# MEMORY.net
KiCad netlist of a schematic drawn in Altium Designer
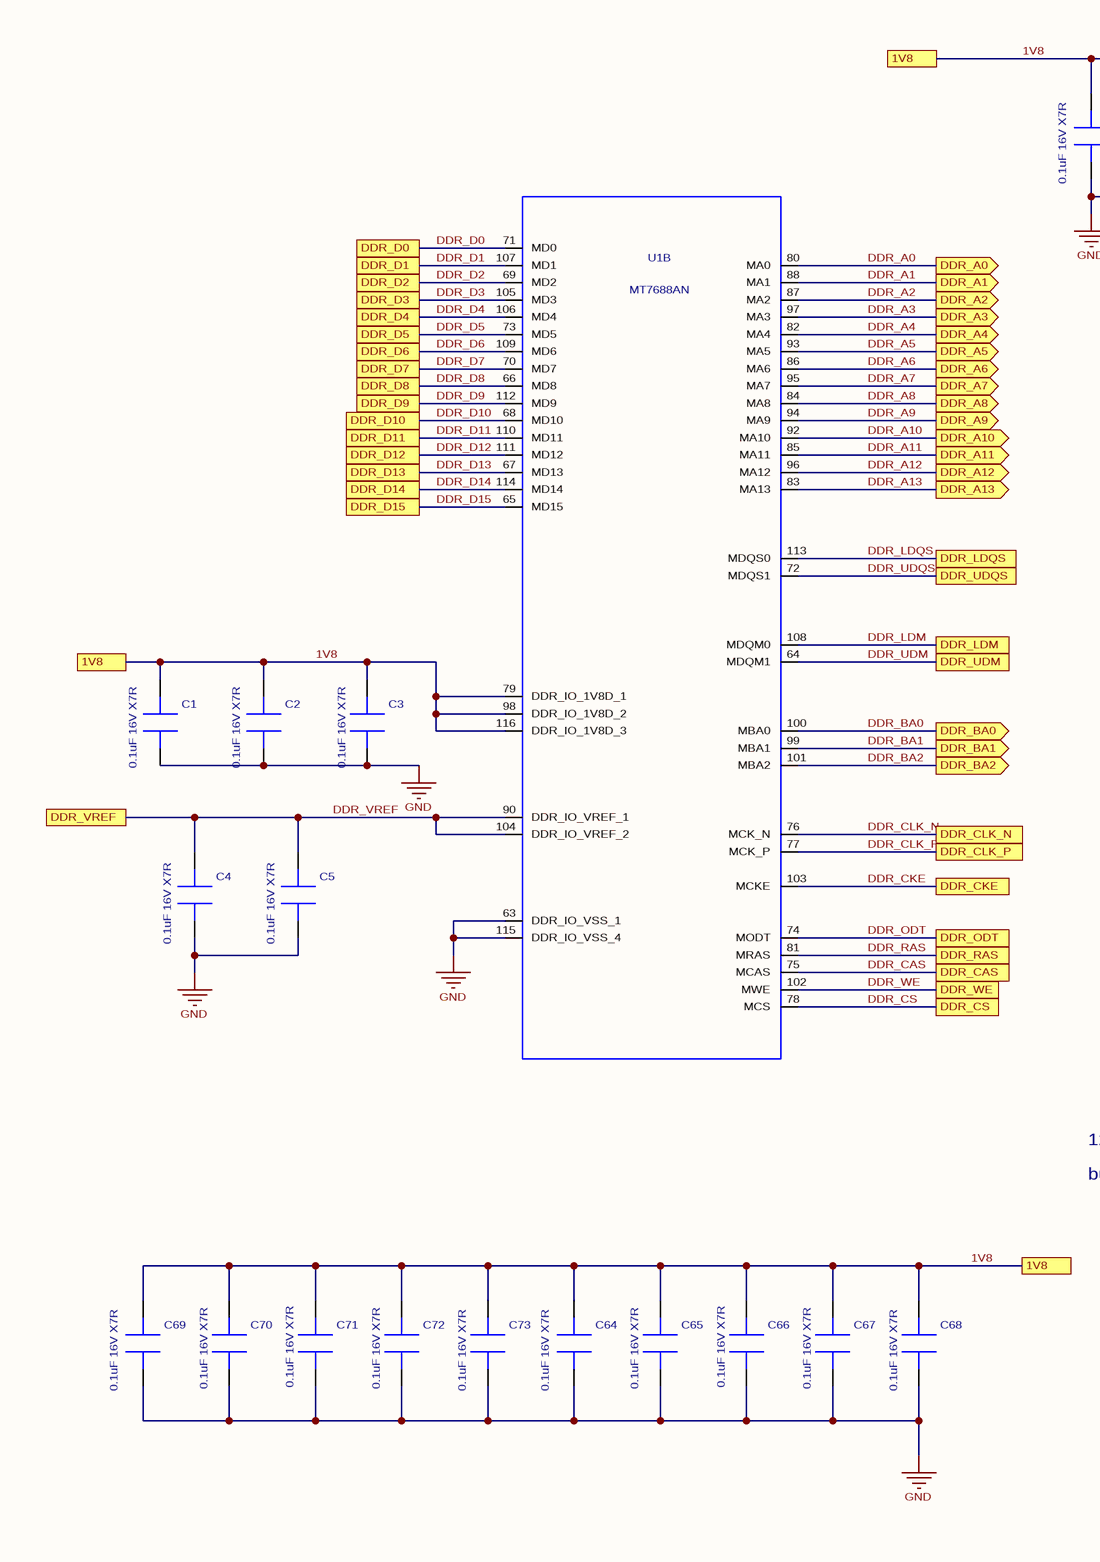
[diagram p0: MEMORY.SchDoc, left]
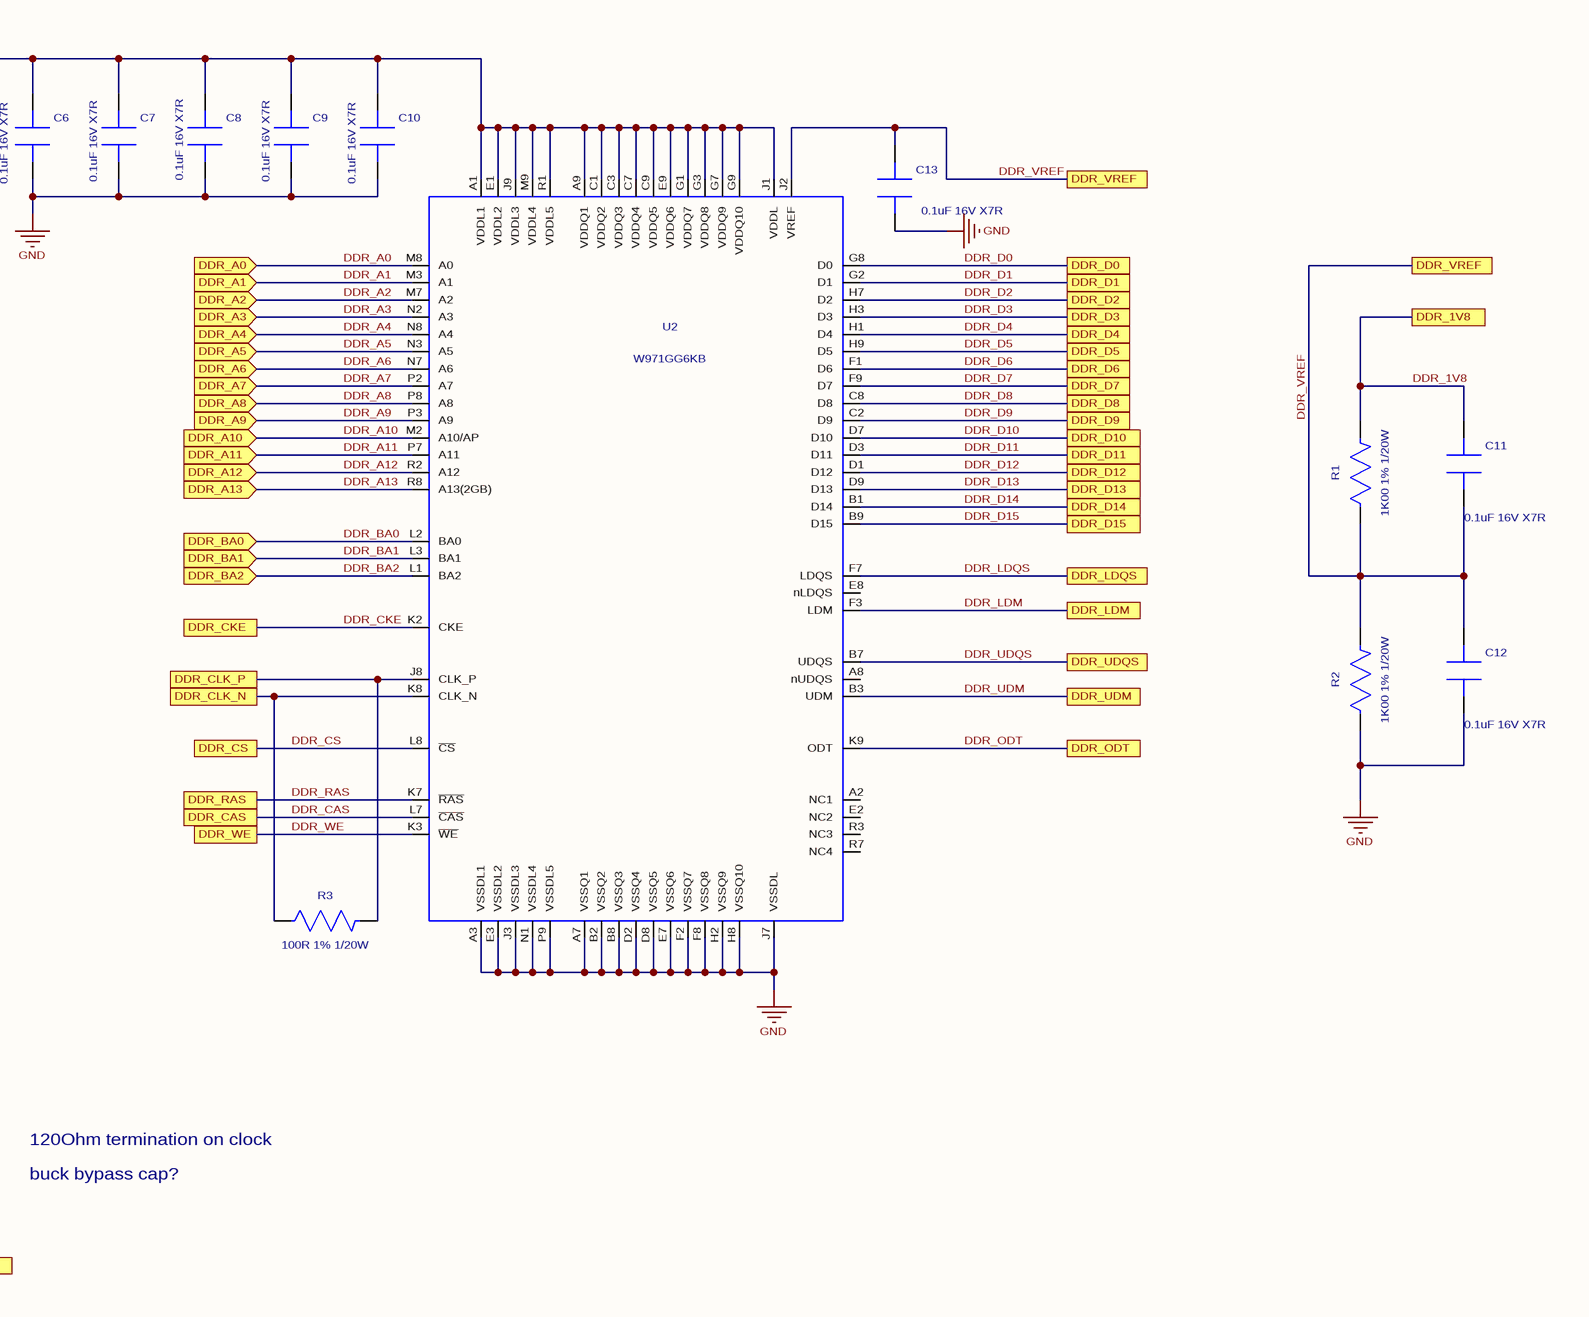
[diagram p1: MEMORY.SchDoc, right]

(export (version "E")
  (design (tool "Eeschema 10.0.6"))
  (components
    (comp (ref "C1")
      (value "0.1uF 16V X7R")
      (footprint "C0201")
      (description "CAP CER 0.1UF 16V X7R 0201")
      (fields
        (field (name "PART NUMBER") "GRM033Z71C104KE14D")
        (field (name "MANUFACTURER") "Murata Electronics")
      )
      (libsource (lib "NetworkModule") (part "CAP0201-104-16V-X7R"))
    )
    (comp (ref "C2")
      (value "0.1uF 16V X7R")
      (footprint "C0201")
      (description "CAP CER 0.1UF 16V X7R 0201")
      (fields
        (field (name "PART NUMBER") "GRM033Z71C104KE14D")
        (field (name "MANUFACTURER") "Murata Electronics")
      )
      (libsource (lib "NetworkModule") (part "CAP0201-104-16V-X7R"))
    )
    (comp (ref "C3")
      (value "0.1uF 16V X7R")
      (footprint "C0201")
      (description "CAP CER 0.1UF 16V X7R 0201")
      (fields
        (field (name "PART NUMBER") "GRM033Z71C104KE14D")
        (field (name "MANUFACTURER") "Murata Electronics")
      )
      (libsource (lib "NetworkModule") (part "CAP0201-104-16V-X7R"))
    )
    (comp (ref "C4")
      (value "0.1uF 16V X7R")
      (footprint "C0201")
      (description "CAP CER 0.1UF 16V X7R 0201")
      (fields
        (field (name "PART NUMBER") "GRM033Z71C104KE14D")
        (field (name "MANUFACTURER") "Murata Electronics")
      )
      (libsource (lib "NetworkModule") (part "CAP0201-104-16V-X7R"))
    )
    (comp (ref "C5")
      (value "0.1uF 16V X7R")
      (footprint "C0201")
      (description "CAP CER 0.1UF 16V X7R 0201")
      (fields
        (field (name "PART NUMBER") "GRM033Z71C104KE14D")
        (field (name "MANUFACTURER") "Murata Electronics")
      )
      (libsource (lib "NetworkModule") (part "CAP0201-104-16V-X7R"))
    )
    (comp (ref "C6")
      (value "0.1uF 16V X7R")
      (footprint "C0201")
      (description "CAP CER 0.1UF 16V X7R 0201")
      (fields
        (field (name "PART NUMBER") "GRM033Z71C104KE14D")
        (field (name "MANUFACTURER") "Murata Electronics")
      )
      (libsource (lib "NetworkModule") (part "CAP0201-104-16V-X7R"))
    )
    (comp (ref "C7")
      (value "0.1uF 16V X7R")
      (footprint "C0201")
      (description "CAP CER 0.1UF 16V X7R 0201")
      (fields
        (field (name "PART NUMBER") "GRM033Z71C104KE14D")
        (field (name "MANUFACTURER") "Murata Electronics")
      )
      (libsource (lib "NetworkModule") (part "CAP0201-104-16V-X7R"))
    )
    (comp (ref "C8")
      (value "0.1uF 16V X7R")
      (footprint "C0201")
      (description "CAP CER 0.1UF 16V X7R 0201")
      (fields
        (field (name "PART NUMBER") "GRM033Z71C104KE14D")
        (field (name "MANUFACTURER") "Murata Electronics")
      )
      (libsource (lib "NetworkModule") (part "CAP0201-104-16V-X7R"))
    )
    (comp (ref "C9")
      (value "0.1uF 16V X7R")
      (footprint "C0201")
      (description "CAP CER 0.1UF 16V X7R 0201")
      (fields
        (field (name "PART NUMBER") "GRM033Z71C104KE14D")
        (field (name "MANUFACTURER") "Murata Electronics")
      )
      (libsource (lib "NetworkModule") (part "CAP0201-104-16V-X7R"))
    )
    (comp (ref "C10")
      (value "0.1uF 16V X7R")
      (footprint "C0201")
      (description "CAP CER 0.1UF 16V X7R 0201")
      (fields
        (field (name "PART NUMBER") "GRM033Z71C104KE14D")
        (field (name "MANUFACTURER") "Murata Electronics")
      )
      (libsource (lib "NetworkModule") (part "CAP0201-104-16V-X7R"))
    )
    (comp (ref "C11")
      (value "0.1uF 16V X7R")
      (footprint "C0201")
      (description "CAP CER 0.1UF 16V X7R 0201")
      (fields
        (field (name "PART NUMBER") "GRM033Z71C104KE14D")
        (field (name "MANUFACTURER") "Murata Electronics")
      )
      (libsource (lib "NetworkModule") (part "CAP0201-104-16V-X7R"))
    )
    (comp (ref "C12")
      (value "0.1uF 16V X7R")
      (footprint "C0201")
      (description "CAP CER 0.1UF 16V X7R 0201")
      (fields
        (field (name "PART NUMBER") "GRM033Z71C104KE14D")
        (field (name "MANUFACTURER") "Murata Electronics")
      )
      (libsource (lib "NetworkModule") (part "CAP0201-104-16V-X7R"))
    )
    (comp (ref "C13")
      (value "0.1uF 16V X7R")
      (footprint "C0201")
      (description "CAP CER 0.1UF 16V X7R 0201")
      (fields
        (field (name "PART NUMBER") "GRM033Z71C104KE14D")
        (field (name "MANUFACTURER") "Murata Electronics")
      )
      (libsource (lib "NetworkModule") (part "CAP0201-104-16V-X7R"))
    )
    (comp (ref "C64")
      (value "0.1uF 16V X7R")
      (footprint "C0201")
      (description "CAP CER 0.1UF 16V X7R 0201")
      (fields
        (field (name "PART NUMBER") "GRM033Z71C104KE14D")
        (field (name "MANUFACTURER") "Murata Electronics")
      )
      (libsource (lib "NetworkModule") (part "CAP0201-104-16V-X7R"))
    )
    (comp (ref "C65")
      (value "0.1uF 16V X7R")
      (footprint "C0201")
      (description "CAP CER 0.1UF 16V X7R 0201")
      (fields
        (field (name "PART NUMBER") "GRM033Z71C104KE14D")
        (field (name "MANUFACTURER") "Murata Electronics")
      )
      (libsource (lib "NetworkModule") (part "CAP0201-104-16V-X7R"))
    )
    (comp (ref "C66")
      (value "0.1uF 16V X7R")
      (footprint "C0201")
      (description "CAP CER 0.1UF 16V X7R 0201")
      (fields
        (field (name "PART NUMBER") "GRM033Z71C104KE14D")
        (field (name "MANUFACTURER") "Murata Electronics")
      )
      (libsource (lib "NetworkModule") (part "CAP0201-104-16V-X7R"))
    )
    (comp (ref "C67")
      (value "0.1uF 16V X7R")
      (footprint "C0201")
      (description "CAP CER 0.1UF 16V X7R 0201")
      (fields
        (field (name "PART NUMBER") "GRM033Z71C104KE14D")
        (field (name "MANUFACTURER") "Murata Electronics")
      )
      (libsource (lib "NetworkModule") (part "CAP0201-104-16V-X7R"))
    )
    (comp (ref "C68")
      (value "0.1uF 16V X7R")
      (footprint "C0201")
      (description "CAP CER 0.1UF 16V X7R 0201")
      (fields
        (field (name "PART NUMBER") "GRM033Z71C104KE14D")
        (field (name "MANUFACTURER") "Murata Electronics")
      )
      (libsource (lib "NetworkModule") (part "CAP0201-104-16V-X7R"))
    )
    (comp (ref "C69")
      (value "0.1uF 16V X7R")
      (footprint "C0201")
      (description "CAP CER 0.1UF 16V X7R 0201")
      (fields
        (field (name "PART NUMBER") "GRM033Z71C104KE14D")
        (field (name "MANUFACTURER") "Murata Electronics")
      )
      (libsource (lib "NetworkModule") (part "CAP0201-104-16V-X7R"))
    )
    (comp (ref "C70")
      (value "0.1uF 16V X7R")
      (footprint "C0201")
      (description "CAP CER 0.1UF 16V X7R 0201")
      (fields
        (field (name "PART NUMBER") "GRM033Z71C104KE14D")
        (field (name "MANUFACTURER") "Murata Electronics")
      )
      (libsource (lib "NetworkModule") (part "CAP0201-104-16V-X7R"))
    )
    (comp (ref "C71")
      (value "0.1uF 16V X7R")
      (footprint "C0201")
      (description "CAP CER 0.1UF 16V X7R 0201")
      (fields
        (field (name "PART NUMBER") "GRM033Z71C104KE14D")
        (field (name "MANUFACTURER") "Murata Electronics")
      )
      (libsource (lib "NetworkModule") (part "CAP0201-104-16V-X7R"))
    )
    (comp (ref "C72")
      (value "0.1uF 16V X7R")
      (footprint "C0201")
      (description "CAP CER 0.1UF 16V X7R 0201")
      (fields
        (field (name "PART NUMBER") "GRM033Z71C104KE14D")
        (field (name "MANUFACTURER") "Murata Electronics")
      )
      (libsource (lib "NetworkModule") (part "CAP0201-104-16V-X7R"))
    )
    (comp (ref "C73")
      (value "0.1uF 16V X7R")
      (footprint "C0201")
      (description "CAP CER 0.1UF 16V X7R 0201")
      (fields
        (field (name "PART NUMBER") "GRM033Z71C104KE14D")
        (field (name "MANUFACTURER") "Murata Electronics")
      )
      (libsource (lib "NetworkModule") (part "CAP0201-104-16V-X7R"))
    )
    (comp (ref "R1")
      (value "1K00 1% 1/20W")
      (footprint "R0201")
      (description "RES 1K OHM 1% 1/20W 0201")
      (fields
        (field (name "PART NUMBER") "RMCF0201FT1K00")
        (field (name "MANUFACTURER") "Stackpole Electronics Inc")
      )
      (libsource (lib "NetworkModule") (part "RES0201-1K00"))
    )
    (comp (ref "R2")
      (value "1K00 1% 1/20W")
      (footprint "R0201")
      (description "RES 1K OHM 1% 1/20W 0201")
      (fields
        (field (name "PART NUMBER") "RMCF0201FT1K00")
        (field (name "MANUFACTURER") "Stackpole Electronics Inc")
      )
      (libsource (lib "NetworkModule") (part "RES0201-1K00"))
    )
    (comp (ref "R3")
      (value "100R 1% 1/20W")
      (footprint "R0201")
      (description "RES 100 OHM 1% 1/20W 0201")
      (fields (field (name "MANUFACTURER") "Yageo") (field (name "PART NUMBER") "RC0201FR-07100RL"))
      (libsource (lib "NetworkModule") (part "RES0201-100R"))
    )
    (comp (ref "U1")
      (value "MT7688AN")
      (footprint "DR-QFN-128")
      (description "580Mhz 32bits Networking Processor")
      (fields (field (name "MANUFACTURER") "MediaTek Inc"))
      (libsource (lib "*") (part "MT7688AN"))
    )
    (comp (ref "U2")
      (value "W971GG6KB")
      (footprint "TWBGA-84_8X12P5_ISI")
      (description "IC DRAM 1GBIT PARALLEL 84WBGA")
      (fields (field (name "PART NUMBER") "W971GG6KB-25 TR"))
      (libsource (lib "NetworkModule") (part "W971GG6KB"))
    )
  )
  (nets
    (net (code "1") (name "/1V8") (class "Default")
      (node (ref "C1") (pin "1") (pinfunction "1_1") (pintype "passive"))
      (node (ref "C10") (pin "1") (pinfunction "1_1") (pintype "passive"))
      (node (ref "C2") (pin "1") (pinfunction "1_1") (pintype "passive"))
      (node (ref "C3") (pin "1") (pinfunction "1_1") (pintype "passive"))
      (node (ref "C6") (pin "1") (pinfunction "1_1") (pintype "passive"))
      (node (ref "C64") (pin "1") (pinfunction "1_1") (pintype "passive"))
      (node (ref "C65") (pin "1") (pinfunction "1_1") (pintype "passive"))
      (node (ref "C66") (pin "1") (pinfunction "1_1") (pintype "passive"))
      (node (ref "C67") (pin "1") (pinfunction "1_1") (pintype "passive"))
      (node (ref "C68") (pin "1") (pinfunction "1_1") (pintype "passive"))
      (node (ref "C69") (pin "1") (pinfunction "1_1") (pintype "passive"))
      (node (ref "C7") (pin "1") (pinfunction "1_1") (pintype "passive"))
      (node (ref "C70") (pin "1") (pinfunction "1_1") (pintype "passive"))
      (node (ref "C71") (pin "1") (pinfunction "1_1") (pintype "passive"))
      (node (ref "C72") (pin "1") (pinfunction "1_1") (pintype "passive"))
      (node (ref "C73") (pin "1") (pinfunction "1_1") (pintype "passive"))
      (node (ref "C8") (pin "1") (pinfunction "1_1") (pintype "passive"))
      (node (ref "C9") (pin "1") (pinfunction "1_1") (pintype "passive"))
      (node (ref "U1") (pin "116") (pinfunction "DDR_IO_1V8D_3_116") (pintype "passive"))
      (node (ref "U1") (pin "79") (pinfunction "DDR_IO_1V8D_1_79") (pintype "passive"))
      (node (ref "U1") (pin "98") (pinfunction "DDR_IO_1V8D_2_98") (pintype "passive"))
      (node (ref "U2") (pin "A1") (pinfunction "VDDL1_A1") (pintype "passive"))
      (node (ref "U2") (pin "A9") (pinfunction "VDDQ1_A9") (pintype "passive"))
      (node (ref "U2") (pin "C1") (pinfunction "VDDQ2_C1") (pintype "passive"))
      (node (ref "U2") (pin "C3") (pinfunction "VDDQ3_C3") (pintype "passive"))
      (node (ref "U2") (pin "C7") (pinfunction "VDDQ4_C7") (pintype "passive"))
      (node (ref "U2") (pin "C9") (pinfunction "VDDQ5_C9") (pintype "passive"))
      (node (ref "U2") (pin "E1") (pinfunction "VDDL2_E1") (pintype "passive"))
      (node (ref "U2") (pin "E9") (pinfunction "VDDQ6_E9") (pintype "passive"))
      (node (ref "U2") (pin "G1") (pinfunction "VDDQ7_G1") (pintype "passive"))
      (node (ref "U2") (pin "G3") (pinfunction "VDDQ8_G3") (pintype "passive"))
      (node (ref "U2") (pin "G7") (pinfunction "VDDQ9_G7") (pintype "passive"))
      (node (ref "U2") (pin "G9") (pinfunction "VDDQ10_G9") (pintype "passive"))
      (node (ref "U2") (pin "J1") (pinfunction "VDDL_J1") (pintype "passive"))
      (node (ref "U2") (pin "J9") (pinfunction "VDDL3_J9") (pintype "passive"))
      (node (ref "U2") (pin "M9") (pinfunction "VDDL4_M9") (pintype "passive"))
      (node (ref "U2") (pin "R1") (pinfunction "VDDL5_R1") (pintype "passive"))
    )
    (net (code "2") (name "/DDR_1V8") (class "Default")
      (node (ref "C11") (pin "1") (pinfunction "1_1") (pintype "passive"))
      (node (ref "R1") (pin "2") (pinfunction "2_2") (pintype "passive"))
    )
    (net (code "3") (name "/DDR_A0") (class "Default")
      (node (ref "U1") (pin "80") (pinfunction "MA0_80") (pintype "passive"))
      (node (ref "U2") (pin "M8") (pinfunction "A0_M8") (pintype "passive"))
    )
    (net (code "4") (name "/DDR_A1") (class "Default")
      (node (ref "U1") (pin "88") (pinfunction "MA1_88") (pintype "passive"))
      (node (ref "U2") (pin "M3") (pinfunction "A1_M3") (pintype "passive"))
    )
    (net (code "5") (name "/DDR_A2") (class "Default")
      (node (ref "U1") (pin "87") (pinfunction "MA2_87") (pintype "passive"))
      (node (ref "U2") (pin "M7") (pinfunction "A2_M7") (pintype "passive"))
    )
    (net (code "6") (name "/DDR_A3") (class "Default")
      (node (ref "U1") (pin "97") (pinfunction "MA3_97") (pintype "passive"))
      (node (ref "U2") (pin "N2") (pinfunction "A3_N2") (pintype "passive"))
    )
    (net (code "7") (name "/DDR_A4") (class "Default")
      (node (ref "U1") (pin "82") (pinfunction "MA4_82") (pintype "passive"))
      (node (ref "U2") (pin "N8") (pinfunction "A4_N8") (pintype "passive"))
    )
    (net (code "8") (name "/DDR_A5") (class "Default")
      (node (ref "U1") (pin "93") (pinfunction "MA5_93") (pintype "passive"))
      (node (ref "U2") (pin "N3") (pinfunction "A5_N3") (pintype "passive"))
    )
    (net (code "9") (name "/DDR_A6") (class "Default")
      (node (ref "U1") (pin "86") (pinfunction "MA6_86") (pintype "passive"))
      (node (ref "U2") (pin "N7") (pinfunction "A6_N7") (pintype "passive"))
    )
    (net (code "10") (name "/DDR_A7") (class "Default")
      (node (ref "U1") (pin "95") (pinfunction "MA7_95") (pintype "passive"))
      (node (ref "U2") (pin "P2") (pinfunction "A7_P2") (pintype "passive"))
    )
    (net (code "11") (name "/DDR_A8") (class "Default")
      (node (ref "U1") (pin "84") (pinfunction "MA8_84") (pintype "passive"))
      (node (ref "U2") (pin "P8") (pinfunction "A8_P8") (pintype "passive"))
    )
    (net (code "12") (name "/DDR_A9") (class "Default")
      (node (ref "U1") (pin "94") (pinfunction "MA9_94") (pintype "passive"))
      (node (ref "U2") (pin "P3") (pinfunction "A9_P3") (pintype "passive"))
    )
    (net (code "13") (name "/DDR_A10") (class "Default")
      (node (ref "U1") (pin "92") (pinfunction "MA10_92") (pintype "passive"))
      (node (ref "U2") (pin "M2") (pinfunction "A10/AP_M2") (pintype "passive"))
    )
    (net (code "14") (name "/DDR_A11") (class "Default")
      (node (ref "U1") (pin "85") (pinfunction "MA11_85") (pintype "passive"))
      (node (ref "U2") (pin "P7") (pinfunction "A11_P7") (pintype "passive"))
    )
    (net (code "15") (name "/DDR_A12") (class "Default")
      (node (ref "U1") (pin "96") (pinfunction "MA12_96") (pintype "passive"))
      (node (ref "U2") (pin "R2") (pinfunction "A12_R2") (pintype "passive"))
    )
    (net (code "16") (name "/DDR_A13") (class "Default")
      (node (ref "U1") (pin "83") (pinfunction "MA13_83") (pintype "passive"))
      (node (ref "U2") (pin "R8") (pinfunction "A13(2GB)_R8") (pintype "passive"))
    )
    (net (code "17") (name "/DDR_BA0") (class "Default")
      (node (ref "U1") (pin "100") (pinfunction "MBA0_100") (pintype "passive"))
      (node (ref "U2") (pin "L2") (pinfunction "BA0_L2") (pintype "passive"))
    )
    (net (code "18") (name "/DDR_BA1") (class "Default")
      (node (ref "U1") (pin "99") (pinfunction "MBA1_99") (pintype "passive"))
      (node (ref "U2") (pin "L3") (pinfunction "BA1_L3") (pintype "passive"))
    )
    (net (code "19") (name "/DDR_BA2") (class "Default")
      (node (ref "U1") (pin "101") (pinfunction "MBA2_101") (pintype "passive"))
      (node (ref "U2") (pin "L1") (pinfunction "BA2_L1") (pintype "passive"))
    )
    (net (code "20") (name "/DDR_CAS") (class "Default")
      (node (ref "U1") (pin "75") (pinfunction "MCAS_75") (pintype "passive"))
      (node (ref "U2") (pin "L7") (pinfunction "CAS_L7") (pintype "passive"))
    )
    (net (code "21") (name "/DDR_CKE") (class "Default")
      (node (ref "U1") (pin "103") (pinfunction "MCKE_103") (pintype "passive"))
      (node (ref "U2") (pin "K2") (pinfunction "CKE_K2") (pintype "passive"))
    )
    (net (code "22") (name "/DDR_CLK_N") (class "Default")
      (node (ref "R3") (pin "1") (pinfunction "1_1") (pintype "passive"))
      (node (ref "U1") (pin "76") (pinfunction "MCK_N_76") (pintype "passive"))
      (node (ref "U2") (pin "K8") (pinfunction "CLK_N_K8") (pintype "passive"))
    )
    (net (code "23") (name "/DDR_CLK_P") (class "Default")
      (node (ref "R3") (pin "2") (pinfunction "2_2") (pintype "passive"))
      (node (ref "U1") (pin "77") (pinfunction "MCK_P_77") (pintype "passive"))
      (node (ref "U2") (pin "J8") (pinfunction "CLK_P_J8") (pintype "passive"))
    )
    (net (code "24") (name "/DDR_CS") (class "Default")
      (node (ref "U1") (pin "78") (pinfunction "MCS_78") (pintype "passive"))
      (node (ref "U2") (pin "L8") (pinfunction "CS_L8") (pintype "passive"))
    )
    (net (code "25") (name "/DDR_D0") (class "Default")
      (node (ref "U1") (pin "71") (pinfunction "MD0_71") (pintype "passive"))
      (node (ref "U2") (pin "G8") (pinfunction "D0_G8") (pintype "passive"))
    )
    (net (code "26") (name "/DDR_D1") (class "Default")
      (node (ref "U1") (pin "107") (pinfunction "MD1_107") (pintype "passive"))
      (node (ref "U2") (pin "G2") (pinfunction "D1_G2") (pintype "passive"))
    )
    (net (code "27") (name "/DDR_D2") (class "Default")
      (node (ref "U1") (pin "69") (pinfunction "MD2_69") (pintype "passive"))
      (node (ref "U2") (pin "H7") (pinfunction "D2_H7") (pintype "passive"))
    )
    (net (code "28") (name "/DDR_D3") (class "Default")
      (node (ref "U1") (pin "105") (pinfunction "MD3_105") (pintype "passive"))
      (node (ref "U2") (pin "H3") (pinfunction "D3_H3") (pintype "passive"))
    )
    (net (code "29") (name "/DDR_D4") (class "Default")
      (node (ref "U1") (pin "106") (pinfunction "MD4_106") (pintype "passive"))
      (node (ref "U2") (pin "H1") (pinfunction "D4_H1") (pintype "passive"))
    )
    (net (code "30") (name "/DDR_D5") (class "Default")
      (node (ref "U1") (pin "73") (pinfunction "MD5_73") (pintype "passive"))
      (node (ref "U2") (pin "H9") (pinfunction "D5_H9") (pintype "passive"))
    )
    (net (code "31") (name "/DDR_D6") (class "Default")
      (node (ref "U1") (pin "109") (pinfunction "MD6_109") (pintype "passive"))
      (node (ref "U2") (pin "F1") (pinfunction "D6_F1") (pintype "passive"))
    )
    (net (code "32") (name "/DDR_D7") (class "Default")
      (node (ref "U1") (pin "70") (pinfunction "MD7_70") (pintype "passive"))
      (node (ref "U2") (pin "F9") (pinfunction "D7_F9") (pintype "passive"))
    )
    (net (code "33") (name "/DDR_D8") (class "Default")
      (node (ref "U1") (pin "66") (pinfunction "MD8_66") (pintype "passive"))
      (node (ref "U2") (pin "C8") (pinfunction "D8_C8") (pintype "passive"))
    )
    (net (code "34") (name "/DDR_D9") (class "Default")
      (node (ref "U1") (pin "112") (pinfunction "MD9_112") (pintype "passive"))
      (node (ref "U2") (pin "C2") (pinfunction "D9_C2") (pintype "passive"))
    )
    (net (code "35") (name "/DDR_D10") (class "Default")
      (node (ref "U1") (pin "68") (pinfunction "MD10_68") (pintype "passive"))
      (node (ref "U2") (pin "D7") (pinfunction "D10_D7") (pintype "passive"))
    )
    (net (code "36") (name "/DDR_D11") (class "Default")
      (node (ref "U1") (pin "110") (pinfunction "MD11_110") (pintype "passive"))
      (node (ref "U2") (pin "D3") (pinfunction "D11_D3") (pintype "passive"))
    )
    (net (code "37") (name "/DDR_D12") (class "Default")
      (node (ref "U1") (pin "111") (pinfunction "MD12_111") (pintype "passive"))
      (node (ref "U2") (pin "D1") (pinfunction "D12_D1") (pintype "passive"))
    )
    (net (code "38") (name "/DDR_D13") (class "Default")
      (node (ref "U1") (pin "67") (pinfunction "MD13_67") (pintype "passive"))
      (node (ref "U2") (pin "D9") (pinfunction "D13_D9") (pintype "passive"))
    )
    (net (code "39") (name "/DDR_D14") (class "Default")
      (node (ref "U1") (pin "114") (pinfunction "MD14_114") (pintype "passive"))
      (node (ref "U2") (pin "B1") (pinfunction "D14_B1") (pintype "passive"))
    )
    (net (code "40") (name "/DDR_D15") (class "Default")
      (node (ref "U1") (pin "65") (pinfunction "MD15_65") (pintype "passive"))
      (node (ref "U2") (pin "B9") (pinfunction "D15_B9") (pintype "passive"))
    )
    (net (code "41") (name "/DDR_LDM") (class "Default")
      (node (ref "U1") (pin "108") (pinfunction "MDQM0_108") (pintype "passive"))
      (node (ref "U2") (pin "F3") (pinfunction "LDM_F3") (pintype "passive"))
    )
    (net (code "42") (name "/DDR_LDQS") (class "Default")
      (node (ref "U1") (pin "113") (pinfunction "MDQS0_113") (pintype "passive"))
      (node (ref "U2") (pin "F7") (pinfunction "LDQS_F7") (pintype "passive"))
    )
    (net (code "43") (name "/DDR_ODT") (class "Default")
      (node (ref "U1") (pin "74") (pinfunction "MODT_74") (pintype "passive"))
      (node (ref "U2") (pin "K9") (pinfunction "ODT_K9") (pintype "passive"))
    )
    (net (code "44") (name "/DDR_RAS") (class "Default")
      (node (ref "U1") (pin "81") (pinfunction "MRAS_81") (pintype "passive"))
      (node (ref "U2") (pin "K7") (pinfunction "RAS_K7") (pintype "passive"))
    )
    (net (code "45") (name "/DDR_UDM") (class "Default")
      (node (ref "U1") (pin "64") (pinfunction "MDQM1_64") (pintype "passive"))
      (node (ref "U2") (pin "B3") (pinfunction "UDM_B3") (pintype "passive"))
    )
    (net (code "46") (name "/DDR_UDQS") (class "Default")
      (node (ref "U1") (pin "72") (pinfunction "MDQS1_72") (pintype "passive"))
      (node (ref "U2") (pin "B7") (pinfunction "UDQS_B7") (pintype "passive"))
    )
    (net (code "47") (name "/DDR_VREF") (class "Default")
      (node (ref "C11") (pin "2") (pinfunction "2_2") (pintype "passive"))
      (node (ref "C12") (pin "1") (pinfunction "1_1") (pintype "passive"))
      (node (ref "C13") (pin "1") (pinfunction "1_1") (pintype "passive"))
      (node (ref "C4") (pin "1") (pinfunction "1_1") (pintype "passive"))
      (node (ref "C5") (pin "1") (pinfunction "1_1") (pintype "passive"))
      (node (ref "R1") (pin "1") (pinfunction "1_1") (pintype "passive"))
      (node (ref "R2") (pin "2") (pinfunction "2_2") (pintype "passive"))
      (node (ref "U1") (pin "104") (pinfunction "DDR_IO_VREF_2_104") (pintype "passive"))
      (node (ref "U1") (pin "90") (pinfunction "DDR_IO_VREF_1_90") (pintype "passive"))
      (node (ref "U2") (pin "J2") (pinfunction "VREF_J2") (pintype "passive"))
    )
    (net (code "48") (name "/DDR_WE") (class "Default")
      (node (ref "U1") (pin "102") (pinfunction "MWE_102") (pintype "passive"))
      (node (ref "U2") (pin "K3") (pinfunction "WE_K3") (pintype "passive"))
    )
    (net (code "49") (name "GND") (class "Default")
      (node (ref "C1") (pin "2") (pinfunction "2_2") (pintype "passive"))
      (node (ref "C10") (pin "2") (pinfunction "2_2") (pintype "passive"))
      (node (ref "C12") (pin "2") (pinfunction "2_2") (pintype "passive"))
      (node (ref "C13") (pin "2") (pinfunction "2_2") (pintype "passive"))
      (node (ref "C2") (pin "2") (pinfunction "2_2") (pintype "passive"))
      (node (ref "C3") (pin "2") (pinfunction "2_2") (pintype "passive"))
      (node (ref "C4") (pin "2") (pinfunction "2_2") (pintype "passive"))
      (node (ref "C5") (pin "2") (pinfunction "2_2") (pintype "passive"))
      (node (ref "C6") (pin "2") (pinfunction "2_2") (pintype "passive"))
      (node (ref "C64") (pin "2") (pinfunction "2_2") (pintype "passive"))
      (node (ref "C65") (pin "2") (pinfunction "2_2") (pintype "passive"))
      (node (ref "C66") (pin "2") (pinfunction "2_2") (pintype "passive"))
      (node (ref "C67") (pin "2") (pinfunction "2_2") (pintype "passive"))
      (node (ref "C68") (pin "2") (pinfunction "2_2") (pintype "passive"))
      (node (ref "C69") (pin "2") (pinfunction "2_2") (pintype "passive"))
      (node (ref "C7") (pin "2") (pinfunction "2_2") (pintype "passive"))
      (node (ref "C70") (pin "2") (pinfunction "2_2") (pintype "passive"))
      (node (ref "C71") (pin "2") (pinfunction "2_2") (pintype "passive"))
      (node (ref "C72") (pin "2") (pinfunction "2_2") (pintype "passive"))
      (node (ref "C73") (pin "2") (pinfunction "2_2") (pintype "passive"))
      (node (ref "C8") (pin "2") (pinfunction "2_2") (pintype "passive"))
      (node (ref "C9") (pin "2") (pinfunction "2_2") (pintype "passive"))
      (node (ref "R2") (pin "1") (pinfunction "1_1") (pintype "passive"))
      (node (ref "U1") (pin "115") (pinfunction "DDR_IO_VSS_4_115") (pintype "passive"))
      (node (ref "U1") (pin "63") (pinfunction "DDR_IO_VSS_1_63") (pintype "passive"))
      (node (ref "U2") (pin "A3") (pinfunction "VSSDL1_A3") (pintype "passive"))
      (node (ref "U2") (pin "A7") (pinfunction "VSSQ1_A7") (pintype "passive"))
      (node (ref "U2") (pin "B2") (pinfunction "VSSQ2_B2") (pintype "passive"))
      (node (ref "U2") (pin "B8") (pinfunction "VSSQ3_B8") (pintype "passive"))
      (node (ref "U2") (pin "D2") (pinfunction "VSSQ4_D2") (pintype "passive"))
      (node (ref "U2") (pin "D8") (pinfunction "VSSQ5_D8") (pintype "passive"))
      (node (ref "U2") (pin "E3") (pinfunction "VSSDL2_E3") (pintype "passive"))
      (node (ref "U2") (pin "E7") (pinfunction "VSSQ6_E7") (pintype "passive"))
      (node (ref "U2") (pin "F2") (pinfunction "VSSQ7_F2") (pintype "passive"))
      (node (ref "U2") (pin "F8") (pinfunction "VSSQ8_F8") (pintype "passive"))
      (node (ref "U2") (pin "H2") (pinfunction "VSSQ9_H2") (pintype "passive"))
      (node (ref "U2") (pin "H8") (pinfunction "VSSQ10_H8") (pintype "passive"))
      (node (ref "U2") (pin "J3") (pinfunction "VSSDL3_J3") (pintype "passive"))
      (node (ref "U2") (pin "J7") (pinfunction "VSSDL_J7") (pintype "passive"))
      (node (ref "U2") (pin "N1") (pinfunction "VSSDL4_N1") (pintype "passive"))
      (node (ref "U2") (pin "P9") (pinfunction "VSSDL5_P9") (pintype "passive"))
    )
    (net (code "50") (name "unconnected-(U2-NC1-PadA2)") (class "Default")
      (node (ref "U2") (pin "A2") (pinfunction "NC1_A2") (pintype "passive"))
    )
    (net (code "51") (name "unconnected-(U2-NC2-PadE2)") (class "Default")
      (node (ref "U2") (pin "E2") (pinfunction "NC2_E2") (pintype "passive"))
    )
    (net (code "52") (name "unconnected-(U2-NC3-PadR3)") (class "Default")
      (node (ref "U2") (pin "R3") (pinfunction "NC3_R3") (pintype "passive"))
    )
    (net (code "53") (name "unconnected-(U2-NC4-PadR7)") (class "Default")
      (node (ref "U2") (pin "R7") (pinfunction "NC4_R7") (pintype "passive"))
    )
    (net (code "54") (name "unconnected-(U2-nLDQS-PadE8)") (class "Default")
      (node (ref "U2") (pin "E8") (pinfunction "nLDQS_E8") (pintype "passive"))
    )
    (net (code "55") (name "unconnected-(U2-nUDQS-PadA8)") (class "Default")
      (node (ref "U2") (pin "A8") (pinfunction "nUDQS_A8") (pintype "passive"))
    )
  )
)
